# Main.net
KiCad netlist of a schematic drawn in Altium Designer
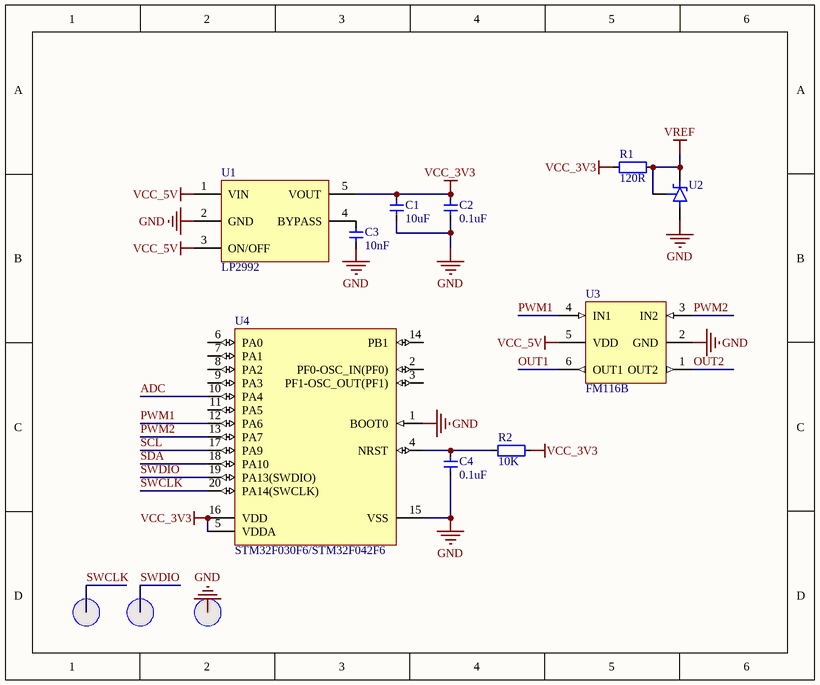
[diagram p0: Main.SchDoc]

(export (version "E")
  (design (tool "Eeschema 10.0.6"))
  (components
    (comp (ref "C1")
      (value "10uF")
      (footprint "CAP_0402")
      (description "Capacitor")
      (libsource (lib "MyPcbLib") (part "电容-0402"))
    )
    (comp (ref "C2")
      (value "0.1uF")
      (footprint "CAP_0402")
      (description "Capacitor")
      (libsource (lib "MyPcbLib") (part "电容-0402"))
    )
    (comp (ref "C3")
      (value "10nF")
      (footprint "CAP_0402")
      (description "Capacitor")
      (libsource (lib "MyPcbLib") (part "电容-0402"))
    )
    (comp (ref "C4")
      (value "0.1uF")
      (footprint "CAP_0402")
      (description "Capacitor")
      (libsource (lib "MyPcbLib") (part "电容-0402"))
    )
    (comp (ref "R1")
      (value "120R")
      (footprint "RES_0402")
      (description "Resistor")
      (libsource (lib "MyPcbLib") (part "电阻-0402"))
    )
    (comp (ref "R2")
      (value "10K")
      (footprint "RES_0402")
      (description "Resistor")
      (libsource (lib "") (part "电阻-0402_1"))
    )
    (comp (ref "T1") (value "测试点") (footprint "TEST_PT") (libsource (lib "MyPcbLib") (part "测试点")))
    (comp (ref "T2") (value "测试点") (footprint "TEST_PT") (libsource (lib "MyPcbLib") (part "测试点")))
    (comp (ref "T3") (value "测试点") (footprint "TEST_PT") (libsource (lib "MyPcbLib") (part "测试点")))
    (comp (ref "U1")
      (value "LP2992")
      (footprint "SOT23-5")
      (description "LDO")
      (libsource (lib "MyPcbLib") (part "LP2992"))
    )
    (comp (ref "U2")
      (value "TL431IDBZT")
      (footprint "SOT23-3")
      (description "Adjustable precision shunt regulator 3-SOT-23 -40 to 85")
      (fields (field (name "MF") "Texas Instruments"))
      (libsource (lib "MyPcbLib") (part "TL431IDBZT"))
    )
    (comp (ref "U3")
      (value "FM116B")
      (footprint "SOT23-6")
      (fields (field (name "PARTNUMBER") "24LC256-I/ST"))
      (libsource (lib "MyPcbLib") (part "FM116B"))
    )
    (comp (ref "U4")
      (value "STM32F030F6/STM32F042F6")
      (footprint "TSSOP-20")
      (fields (field (name "PARTNUMBER") "STM32F030F4P6"))
      (libsource (lib "MyPcbLib") (part "STM32F030F4P6"))
    )
  )
  (nets
    (net (code "1") (name "/ADC") (class "Default")
      (node (ref "U4") (pin "10") (pinfunction "PA4_10") (pintype "bidirectional"))
    )
    (net (code "2") (name "/OUT1") (class "Default")
      (node (ref "U3") (pin "6") (pinfunction "OUT1_6") (pintype "output"))
    )
    (net (code "3") (name "/OUT2") (class "Default")
      (node (ref "U3") (pin "1") (pinfunction "OUT2_1") (pintype "output"))
    )
    (net (code "4") (name "/PWM1") (class "Default")
      (node (ref "U3") (pin "4") (pinfunction "IN1_4") (pintype "input"))
      (node (ref "U4") (pin "12") (pinfunction "PA6_12") (pintype "bidirectional"))
    )
    (net (code "5") (name "/PWM2") (class "Default")
      (node (ref "U3") (pin "3") (pinfunction "IN2_3") (pintype "input"))
      (node (ref "U4") (pin "13") (pinfunction "PA7_13") (pintype "bidirectional"))
    )
    (net (code "6") (name "/SCL") (class "Default")
      (node (ref "U4") (pin "17") (pinfunction "PA9_17") (pintype "bidirectional"))
    )
    (net (code "7") (name "/SDA") (class "Default")
      (node (ref "U4") (pin "18") (pinfunction "PA10_18") (pintype "bidirectional"))
    )
    (net (code "8") (name "/SWCLK") (class "Default")
      (node (ref "T1") (pin "0") (pinfunction "0_0") (pintype "passive"))
      (node (ref "U4") (pin "20") (pinfunction "PA14(SWCLK)_20") (pintype "bidirectional"))
    )
    (net (code "9") (name "/SWDIO") (class "Default")
      (node (ref "T2") (pin "0") (pinfunction "0_0") (pintype "passive"))
      (node (ref "U4") (pin "19") (pinfunction "PA13(SWDIO)_19") (pintype "bidirectional"))
    )
    (net (code "10") (name "GND") (class "Default")
      (node (ref "C1") (pin "1") (pinfunction "1_1") (pintype "passive"))
      (node (ref "C2") (pin "1") (pinfunction "1_1") (pintype "passive"))
      (node (ref "C3") (pin "2") (pinfunction "2_2") (pintype "passive"))
      (node (ref "C4") (pin "1") (pinfunction "1_1") (pintype "passive"))
      (node (ref "T3") (pin "0") (pinfunction "0_0") (pintype "passive"))
      (node (ref "U1") (pin "2") (pinfunction "GND_2") (pintype "passive"))
      (node (ref "U2") (pin "3") (pinfunction "ANODE_3") (pintype "passive"))
      (node (ref "U3") (pin "2") (pinfunction "GND_2") (pintype "power_in"))
      (node (ref "U4") (pin "1") (pinfunction "BOOT0_1") (pintype "input"))
      (node (ref "U4") (pin "15") (pinfunction "VSS_15") (pintype "power_in"))
    )
    (net (code "11") (name "Net-(U1-BYPASS)") (class "Default")
      (node (ref "C3") (pin "1") (pinfunction "1_1") (pintype "passive"))
      (node (ref "U1") (pin "4") (pinfunction "BYPASS_4") (pintype "passive"))
    )
    (net (code "12") (name "Net-(U4-NRST)") (class "Default")
      (node (ref "C4") (pin "2") (pinfunction "2_2") (pintype "passive"))
      (node (ref "R2") (pin "2") (pinfunction "2_2") (pintype "passive"))
      (node (ref "U4") (pin "4") (pinfunction "NRST_4") (pintype "bidirectional"))
    )
    (net (code "13") (name "VCC_3V3") (class "Default")
      (node (ref "C1") (pin "2") (pinfunction "2_2") (pintype "passive"))
      (node (ref "C2") (pin "2") (pinfunction "2_2") (pintype "passive"))
      (node (ref "R1") (pin "1") (pinfunction "1_1") (pintype "passive"))
      (node (ref "R2") (pin "1") (pinfunction "1_1") (pintype "passive"))
      (node (ref "U1") (pin "5") (pinfunction "VOUT_5") (pintype "passive"))
      (node (ref "U4") (pin "16") (pinfunction "VDD_16") (pintype "power_in"))
      (node (ref "U4") (pin "5") (pinfunction "VDDA_5") (pintype "power_in"))
    )
    (net (code "14") (name "VCC_5V") (class "Default")
      (node (ref "U1") (pin "1") (pinfunction "VIN_1") (pintype "passive"))
      (node (ref "U1") (pin "3") (pinfunction "ON/OFF_3") (pintype "passive"))
      (node (ref "U3") (pin "5") (pinfunction "VDD_5") (pintype "power_in"))
    )
    (net (code "15") (name "VREF") (class "Default")
      (node (ref "R1") (pin "2") (pinfunction "2_2") (pintype "passive"))
      (node (ref "U2") (pin "1") (pinfunction "CATHODE_1") (pintype "passive"))
      (node (ref "U2") (pin "2") (pinfunction "REF_2") (pintype "passive"))
    )
    (net (code "16") (name "unconnected-(U4-PA0-Pad6)") (class "Default")
      (node (ref "U4") (pin "6") (pinfunction "PA0_6") (pintype "bidirectional"))
    )
    (net (code "17") (name "unconnected-(U4-PA1-Pad7)") (class "Default")
      (node (ref "U4") (pin "7") (pinfunction "PA1_7") (pintype "bidirectional"))
    )
    (net (code "18") (name "unconnected-(U4-PA2-Pad8)") (class "Default")
      (node (ref "U4") (pin "8") (pinfunction "PA2_8") (pintype "bidirectional"))
    )
    (net (code "19") (name "unconnected-(U4-PA3-Pad9)") (class "Default")
      (node (ref "U4") (pin "9") (pinfunction "PA3_9") (pintype "bidirectional"))
    )
    (net (code "20") (name "unconnected-(U4-PA5-Pad11)") (class "Default")
      (node (ref "U4") (pin "11") (pinfunction "PA5_11") (pintype "bidirectional"))
    )
    (net (code "21") (name "unconnected-(U4-PB1-Pad14)") (class "Default")
      (node (ref "U4") (pin "14") (pinfunction "PB1_14") (pintype "bidirectional"))
    )
    (net (code "22") (name "unconnected-(U4-PF0-OSC_IN(PF0)-Pad2)") (class "Default")
      (node (ref "U4") (pin "2") (pinfunction "PF0-OSC_IN(PF0)_2") (pintype "bidirectional"))
    )
    (net (code "23") (name "unconnected-(U4-PF1-OSC_OUT(PF1)-Pad3)") (class "Default")
      (node (ref "U4") (pin "3") (pinfunction "PF1-OSC_OUT(PF1)_3") (pintype "bidirectional"))
    )
  )
)
